# RCM-Comm_v3_E.net
KiCad netlist of a schematic drawn in EAGLE
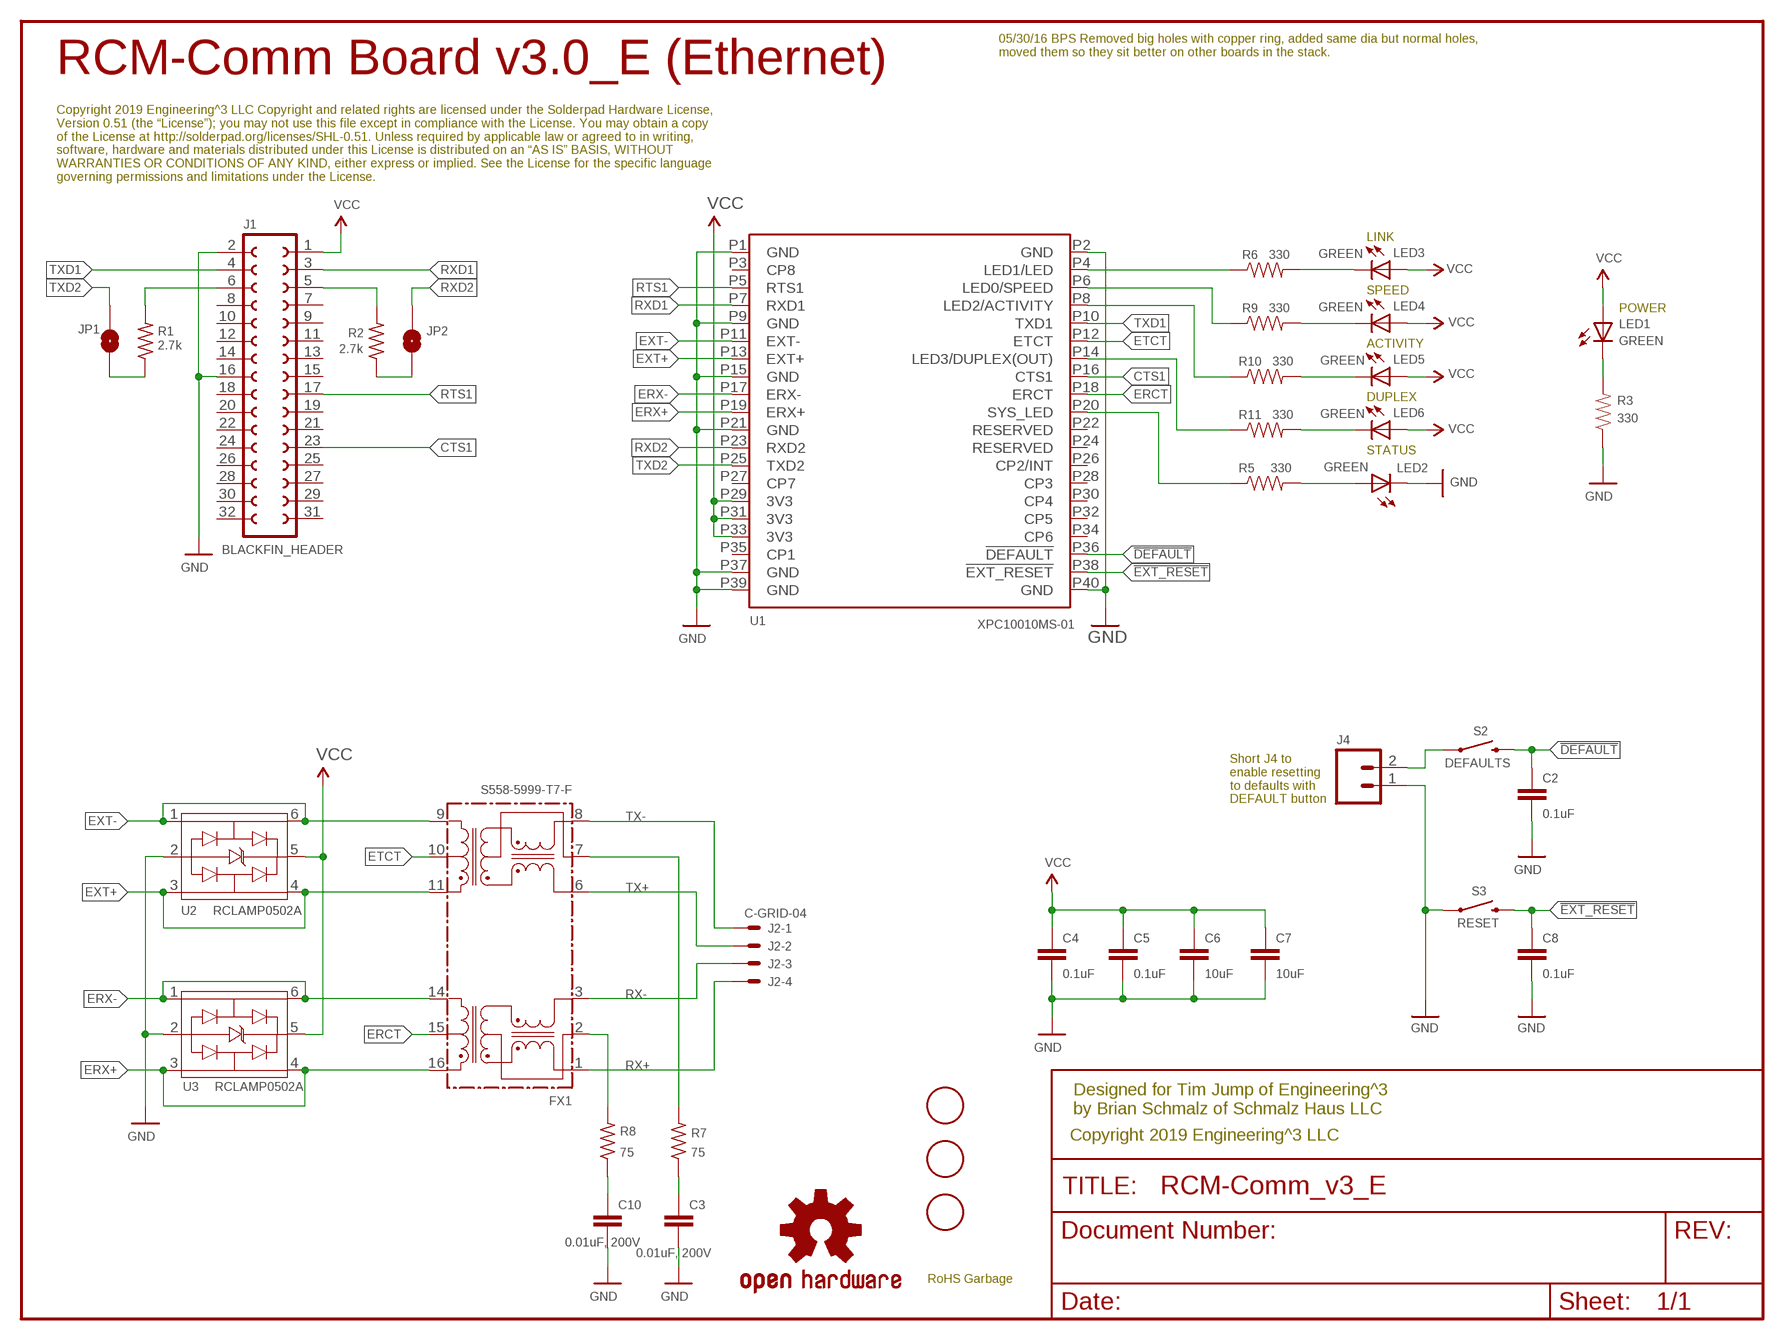
[diagram p0: schematic, sheet 1]

(export (version "E")
  (design (tool "Eeschema 10.0.6"))
  (components
    (comp (ref "C2")
      (value "0.1uF")
      (footprint "eagle-import:0603-CAP")
      (libsource (lib "eagle-import") (part "0.1UF-25V(+80/-20%)(0603)"))
    )
    (comp (ref "C3")
      (value "0.01uF, 200V")
      (footprint "eagle-import:0603-CAP")
      (libsource (lib "eagle-import") (part "CAP0603-CAP"))
    )
    (comp (ref "C4")
      (value "0.1uF")
      (footprint "eagle-import:0603-CAP")
      (libsource (lib "eagle-import") (part "0.1UF-25V(+80/-20%)(0603)"))
    )
    (comp (ref "C5")
      (value "0.1uF")
      (footprint "eagle-import:0603-CAP")
      (libsource (lib "eagle-import") (part "0.1UF-25V(+80/-20%)(0603)"))
    )
    (comp (ref "C6")
      (value "10uF")
      (footprint "eagle-import:0603-CAP")
      (libsource (lib "eagle-import") (part "10UF-6.3V-20%(0603)"))
    )
    (comp (ref "C7")
      (value "10uF")
      (footprint "eagle-import:0603-CAP")
      (libsource (lib "eagle-import") (part "10UF-6.3V-20%(0603)"))
    )
    (comp (ref "C8")
      (value "0.1uF")
      (footprint "eagle-import:0603-CAP")
      (libsource (lib "eagle-import") (part "0.1UF-25V(+80/-20%)(0603)"))
    )
    (comp (ref "C10")
      (value "0.01uF, 200V")
      (footprint "eagle-import:0603-CAP")
      (libsource (lib "eagle-import") (part "CAP0603-CAP"))
    )
    (comp (ref "FID1")
      (value "FIDUCIAL")
      (footprint "eagle-import:FIDUCIAL_1MM")
      (libsource (lib "eagle-import") (part "FIDUCIAL"))
    )
    (comp (ref "FID2")
      (value "FIDUCIAL")
      (footprint "eagle-import:FIDUCIAL_1MM")
      (libsource (lib "eagle-import") (part "FIDUCIAL"))
    )
    (comp (ref "FID3")
      (value "FIDUCIAL")
      (footprint "eagle-import:FIDUCIAL_1MM")
      (libsource (lib "eagle-import") (part "FIDUCIAL"))
    )
    (comp (ref "FX1")
      (value "S558-5999-T7-F")
      (footprint "eagle-import:N5")
      (libsource (lib "eagle-import") (part "TG110-E050N5"))
    )
    (comp (ref "J1")
      (value "BLACKFIN_HEADER")
      (footprint "eagle-import:2X16")
      (libsource (lib "eagle-import") (part "BLACKFIN_HEADER"))
    )
    (comp (ref "J2-")
      (value "C-GRID-04")
      (footprint "eagle-import:70555-04")
      (libsource (lib "eagle-import") (part "C-GRID-04"))
    )
    (comp (ref "J4")
      (value "M02LOCK")
      (footprint "eagle-import:1X02_LOCK")
      (libsource (lib "eagle-import") (part "M02LOCK"))
    )
    (comp (ref "JP1")
      (value "JUMPER-PAD-2-NOROUND")
      (footprint "eagle-import:PAD-JUMPER-2-NO_YES_SILK_ROUND")
      (libsource (lib "eagle-import") (part "JUMPER-PAD-2-NOROUND"))
    )
    (comp (ref "JP2")
      (value "JUMPER-PAD-2-NOROUND")
      (footprint "eagle-import:PAD-JUMPER-2-NO_YES_SILK_ROUND")
      (libsource (lib "eagle-import") (part "JUMPER-PAD-2-NOROUND"))
    )
    (comp (ref "LED1")
      (value "GREEN")
      (footprint "eagle-import:LED-0603")
      (libsource (lib "eagle-import") (part "LED0603"))
    )
    (comp (ref "LED2")
      (value "GREEN")
      (footprint "eagle-import:LED-0603")
      (libsource (lib "eagle-import") (part "LED0603"))
    )
    (comp (ref "LED3")
      (value "GREEN")
      (footprint "eagle-import:LED-0603")
      (libsource (lib "eagle-import") (part "LED0603"))
    )
    (comp (ref "LED4")
      (value "GREEN")
      (footprint "eagle-import:LED-0603")
      (libsource (lib "eagle-import") (part "LED0603"))
    )
    (comp (ref "LED5")
      (value "GREEN")
      (footprint "eagle-import:LED-0603")
      (libsource (lib "eagle-import") (part "LED0603"))
    )
    (comp (ref "LED6")
      (value "GREEN")
      (footprint "eagle-import:LED-0603")
      (libsource (lib "eagle-import") (part "LED0603"))
    )
    (comp (ref "LOGO1")
      (value "OSHW-LOGOM")
      (footprint "eagle-import:OSHW-LOGO-M")
      (libsource (lib "eagle-import") (part "OSHW-LOGOM"))
    )
    (comp (ref "R1")
      (value "2.7k")
      (footprint "eagle-import:R0603")
      (libsource (lib "eagle-import") (part "R-US_R0603"))
    )
    (comp (ref "R2")
      (value "2.7k")
      (footprint "eagle-import:R0603")
      (libsource (lib "eagle-import") (part "R-US_R0603"))
    )
    (comp (ref "R3")
      (value "330")
      (footprint "eagle-import:0603-RES")
      (libsource (lib "eagle-import") (part "RESISTOR0603-RES"))
    )
    (comp (ref "R5")
      (value "330")
      (footprint "eagle-import:0603-RES")
      (libsource (lib "eagle-import") (part "RESISTOR0603-RES"))
    )
    (comp (ref "R6")
      (value "330")
      (footprint "eagle-import:0603-RES")
      (libsource (lib "eagle-import") (part "RESISTOR0603-RES"))
    )
    (comp (ref "R7")
      (value "75")
      (footprint "eagle-import:R0603")
      (libsource (lib "eagle-import") (part "R-US_R0603"))
    )
    (comp (ref "R8")
      (value "75")
      (footprint "eagle-import:R0603")
      (libsource (lib "eagle-import") (part "R-US_R0603"))
    )
    (comp (ref "R9")
      (value "330")
      (footprint "eagle-import:0603-RES")
      (libsource (lib "eagle-import") (part "RESISTOR0603-RES"))
    )
    (comp (ref "R10")
      (value "330")
      (footprint "eagle-import:0603-RES")
      (libsource (lib "eagle-import") (part "RESISTOR0603-RES"))
    )
    (comp (ref "R11")
      (value "330")
      (footprint "eagle-import:0603-RES")
      (libsource (lib "eagle-import") (part "RESISTOR0603-RES"))
    )
    (comp (ref "S2")
      (value "DEFAULTS")
      (footprint "eagle-import:TACTILE-SWITCH-SMD")
      (libsource (lib "eagle-import") (part "SWITCH-MOMENTARY-2SMD"))
    )
    (comp (ref "S3")
      (value "RESET")
      (footprint "eagle-import:TACTILE-SWITCH-SMD")
      (libsource (lib "eagle-import") (part "SWITCH-MOMENTARY-2SMD"))
    )
    (comp (ref "U$3")
      (value "ROHS_GARBAGE")
      (footprint "eagle-import:ROHS_GARBAGE_5MM")
      (libsource (lib "eagle-import") (part "ROHS_GARBAGE"))
    )
    (comp (ref "U1")
      (value "XPC10010MS-01")
      (footprint "eagle-import:LANTRONIX_XPICO")
      (libsource (lib "eagle-import") (part "LANTRONIX_XPICO"))
    )
    (comp (ref "U2")
      (value "RCLAMP0502A")
      (footprint "eagle-import:SC-89")
      (libsource (lib "eagle-import") (part "RCLAMP0502A"))
    )
    (comp (ref "U3")
      (value "RCLAMP0502A")
      (footprint "eagle-import:SC-89")
      (libsource (lib "eagle-import") (part "RCLAMP0502A"))
    )
  )
  (nets
    (net (code "1") (name "/RX+") (class "Default")
      (node (ref "FX1") (pin "1") (pinfunction "1_1") (pintype "passive"))
      (node (ref "J2-") (pin "4") (pinfunction "S_4") (pintype "passive"))
    )
    (net (code "2") (name "/RX-") (class "Default")
      (node (ref "FX1") (pin "3") (pinfunction "3_3") (pintype "passive"))
      (node (ref "J2-") (pin "3") (pinfunction "S_3") (pintype "passive"))
    )
    (net (code "3") (name "/TX+") (class "Default")
      (node (ref "FX1") (pin "6") (pinfunction "6_6") (pintype "passive"))
      (node (ref "J2-") (pin "2") (pinfunction "S_2") (pintype "passive"))
    )
    (net (code "4") (name "/TX-") (class "Default")
      (node (ref "FX1") (pin "8") (pinfunction "8_8") (pintype "passive"))
      (node (ref "J2-") (pin "1") (pinfunction "S_1") (pintype "passive"))
    )
    (net (code "5") (name "/~{DEFAULT}") (class "Default")
      (node (ref "C2") (pin "1") (pinfunction "1_1") (pintype "passive"))
      (node (ref "S2") (pin "3") (pinfunction "2_3") (pintype "passive"))
      (node (ref "U1") (pin "P36") (pinfunction "~{DEFAULT}_P36") (pintype "bidirectional"))
    )
    (net (code "6") (name "/~{EXT_RESET}") (class "Default")
      (node (ref "C8") (pin "1") (pinfunction "1_1") (pintype "passive"))
      (node (ref "S3") (pin "3") (pinfunction "2_3") (pintype "passive"))
      (node (ref "U1") (pin "P38") (pinfunction "~{EXT_RESET}_P38") (pintype "bidirectional"))
    )
    (net (code "7") (name "CTS1") (class "Default")
      (node (ref "J1") (pin "23") (pinfunction "GP6_23") (pintype "passive"))
      (node (ref "U1") (pin "P16") (pinfunction "CTS1_P16") (pintype "bidirectional"))
    )
    (net (code "8") (name "ERCT") (class "Default")
      (node (ref "FX1") (pin "15") (pinfunction "15_15") (pintype "passive"))
      (node (ref "U1") (pin "P18") (pinfunction "ERCT_P18") (pintype "bidirectional"))
    )
    (net (code "9") (name "ERX+") (class "Default")
      (node (ref "FX1") (pin "16") (pinfunction "16_16") (pintype "passive"))
      (node (ref "U1") (pin "P19") (pinfunction "ERX+_P19") (pintype "bidirectional"))
      (node (ref "U3") (pin "3") (pinfunction "P$3_3") (pintype "bidirectional"))
      (node (ref "U3") (pin "4") (pinfunction "P$4_4") (pintype "bidirectional"))
    )
    (net (code "10") (name "ERX-") (class "Default")
      (node (ref "FX1") (pin "14") (pinfunction "14_14") (pintype "passive"))
      (node (ref "U1") (pin "P17") (pinfunction "ERX-_P17") (pintype "bidirectional"))
      (node (ref "U3") (pin "1") (pinfunction "P$1_1") (pintype "bidirectional"))
      (node (ref "U3") (pin "6") (pinfunction "P$6_6") (pintype "bidirectional"))
    )
    (net (code "11") (name "ETCT") (class "Default")
      (node (ref "FX1") (pin "10") (pinfunction "10_10") (pintype "passive"))
      (node (ref "U1") (pin "P12") (pinfunction "ETCT_P12") (pintype "bidirectional"))
    )
    (net (code "12") (name "EXT+") (class "Default")
      (node (ref "FX1") (pin "11") (pinfunction "11_11") (pintype "passive"))
      (node (ref "U1") (pin "P13") (pinfunction "EXT+_P13") (pintype "bidirectional"))
      (node (ref "U2") (pin "3") (pinfunction "P$3_3") (pintype "bidirectional"))
      (node (ref "U2") (pin "4") (pinfunction "P$4_4") (pintype "bidirectional"))
    )
    (net (code "13") (name "EXT-") (class "Default")
      (node (ref "FX1") (pin "9") (pinfunction "9_9") (pintype "passive"))
      (node (ref "U1") (pin "P11") (pinfunction "EXT-_P11") (pintype "bidirectional"))
      (node (ref "U2") (pin "1") (pinfunction "P$1_1") (pintype "bidirectional"))
      (node (ref "U2") (pin "6") (pinfunction "P$6_6") (pintype "bidirectional"))
    )
    (net (code "14") (name "GND") (class "Default")
      (node (ref "C10") (pin "2") (pinfunction "2_2") (pintype "passive"))
      (node (ref "C2") (pin "2") (pinfunction "2_2") (pintype "passive"))
      (node (ref "C3") (pin "2") (pinfunction "2_2") (pintype "passive"))
      (node (ref "C4") (pin "2") (pinfunction "2_2") (pintype "passive"))
      (node (ref "C5") (pin "2") (pinfunction "2_2") (pintype "passive"))
      (node (ref "C6") (pin "2") (pinfunction "2_2") (pintype "passive"))
      (node (ref "C7") (pin "2") (pinfunction "2_2") (pintype "passive"))
      (node (ref "C8") (pin "2") (pinfunction "2_2") (pintype "passive"))
      (node (ref "J1") (pin "16") (pinfunction "GND16_16") (pintype "passive"))
      (node (ref "J1") (pin "2") (pinfunction "GND_2") (pintype "passive"))
      (node (ref "J4") (pin "1") (pinfunction "1_1") (pintype "passive"))
      (node (ref "LED2") (pin "C") (pinfunction "C_C") (pintype "passive"))
      (node (ref "R3") (pin "1") (pinfunction "1_1") (pintype "passive"))
      (node (ref "S3") (pin "1") (pinfunction "1_1") (pintype "passive"))
      (node (ref "U1") (pin "P1") (pinfunction "GND_P1") (pintype "bidirectional"))
      (node (ref "U1") (pin "P15") (pinfunction "GND_P15") (pintype "bidirectional"))
      (node (ref "U1") (pin "P2") (pinfunction "GND_P2") (pintype "bidirectional"))
      (node (ref "U1") (pin "P21") (pinfunction "GND_P21") (pintype "bidirectional"))
      (node (ref "U1") (pin "P37") (pinfunction "GND_P37") (pintype "bidirectional"))
      (node (ref "U1") (pin "P39") (pinfunction "GND_P39") (pintype "bidirectional"))
      (node (ref "U1") (pin "P40") (pinfunction "GND_P40") (pintype "bidirectional"))
      (node (ref "U1") (pin "P9") (pinfunction "GND_P9") (pintype "bidirectional"))
      (node (ref "U2") (pin "2") (pinfunction "P$2_2") (pintype "bidirectional"))
      (node (ref "U3") (pin "2") (pinfunction "P$2_2") (pintype "bidirectional"))
    )
    (net (code "15") (name "Net-(C3-Pad1)") (class "Default")
      (node (ref "C3") (pin "1") (pinfunction "1_1") (pintype "passive"))
      (node (ref "R7") (pin "1") (pinfunction "1_1") (pintype "passive"))
    )
    (net (code "16") (name "Net-(C10-Pad1)") (class "Default")
      (node (ref "C10") (pin "1") (pinfunction "1_1") (pintype "passive"))
      (node (ref "R8") (pin "1") (pinfunction "1_1") (pintype "passive"))
    )
    (net (code "17") (name "Net-(FX1-Pad2)") (class "Default")
      (node (ref "FX1") (pin "2") (pinfunction "2_2") (pintype "passive"))
      (node (ref "R8") (pin "2") (pinfunction "2_2") (pintype "passive"))
    )
    (net (code "18") (name "Net-(FX1-Pad7)") (class "Default")
      (node (ref "FX1") (pin "7") (pinfunction "7_7") (pintype "passive"))
      (node (ref "R7") (pin "2") (pinfunction "2_2") (pintype "passive"))
    )
    (net (code "19") (name "Net-(J1-RX1)") (class "Default")
      (node (ref "J1") (pin "6") (pinfunction "RX1_6") (pintype "passive"))
      (node (ref "R1") (pin "2") (pinfunction "2_2") (pintype "passive"))
    )
    (net (code "20") (name "Net-(J1-TX1)") (class "Default")
      (node (ref "J1") (pin "5") (pinfunction "TX1_5") (pintype "passive"))
      (node (ref "R2") (pin "2") (pinfunction "2_2") (pintype "passive"))
    )
    (net (code "21") (name "Net-(J4-Pad2)") (class "Default")
      (node (ref "J4") (pin "2") (pinfunction "2_2") (pintype "passive"))
      (node (ref "S2") (pin "1") (pinfunction "1_1") (pintype "passive"))
    )
    (net (code "22") (name "Net-(JP1-Pad2)") (class "Default")
      (node (ref "JP1") (pin "2") (pinfunction "2_2") (pintype "passive"))
      (node (ref "R1") (pin "1") (pinfunction "1_1") (pintype "passive"))
    )
    (net (code "23") (name "Net-(JP2-Pad1)") (class "Default")
      (node (ref "JP2") (pin "1") (pinfunction "1_1") (pintype "passive"))
      (node (ref "R2") (pin "1") (pinfunction "1_1") (pintype "passive"))
    )
    (net (code "24") (name "Net-(LED1-PadC)") (class "Default")
      (node (ref "LED1") (pin "C") (pinfunction "C_C") (pintype "passive"))
      (node (ref "R3") (pin "2") (pinfunction "2_2") (pintype "passive"))
    )
    (net (code "25") (name "Net-(LED2-PadA)") (class "Default")
      (node (ref "LED2") (pin "A") (pinfunction "A_A") (pintype "passive"))
      (node (ref "R5") (pin "2") (pinfunction "2_2") (pintype "passive"))
    )
    (net (code "26") (name "Net-(LED3-PadC)") (class "Default")
      (node (ref "LED3") (pin "C") (pinfunction "C_C") (pintype "passive"))
      (node (ref "R6") (pin "2") (pinfunction "2_2") (pintype "passive"))
    )
    (net (code "27") (name "Net-(LED4-PadC)") (class "Default")
      (node (ref "LED4") (pin "C") (pinfunction "C_C") (pintype "passive"))
      (node (ref "R9") (pin "2") (pinfunction "2_2") (pintype "passive"))
    )
    (net (code "28") (name "Net-(LED5-PadC)") (class "Default")
      (node (ref "LED5") (pin "C") (pinfunction "C_C") (pintype "passive"))
      (node (ref "R10") (pin "2") (pinfunction "2_2") (pintype "passive"))
    )
    (net (code "29") (name "Net-(LED6-PadC)") (class "Default")
      (node (ref "LED6") (pin "C") (pinfunction "C_C") (pintype "passive"))
      (node (ref "R11") (pin "2") (pinfunction "2_2") (pintype "passive"))
    )
    (net (code "30") (name "Net-(U1-LED0{slash}SPEED)") (class "Default")
      (node (ref "R9") (pin "1") (pinfunction "1_1") (pintype "passive"))
      (node (ref "U1") (pin "P6") (pinfunction "LED0/SPEED_P6") (pintype "bidirectional"))
    )
    (net (code "31") (name "Net-(U1-LED1{slash}LED)") (class "Default")
      (node (ref "R6") (pin "1") (pinfunction "1_1") (pintype "passive"))
      (node (ref "U1") (pin "P4") (pinfunction "LED1/LED_P4") (pintype "bidirectional"))
    )
    (net (code "32") (name "Net-(U1-LED2{slash}ACTIVITY)") (class "Default")
      (node (ref "R10") (pin "1") (pinfunction "1_1") (pintype "passive"))
      (node (ref "U1") (pin "P8") (pinfunction "LED2/ACTIVITY_P8") (pintype "bidirectional"))
    )
    (net (code "33") (name "Net-(U1-LED3{slash}DUPLEX(OUT))") (class "Default")
      (node (ref "R11") (pin "1") (pinfunction "1_1") (pintype "passive"))
      (node (ref "U1") (pin "P14") (pinfunction "LED3/DUPLEX(OUT)_P14") (pintype "bidirectional"))
    )
    (net (code "34") (name "Net-(U1-SYS_LED)") (class "Default")
      (node (ref "R5") (pin "1") (pinfunction "1_1") (pintype "passive"))
      (node (ref "U1") (pin "P20") (pinfunction "SYS_LED_P20") (pintype "bidirectional"))
    )
    (net (code "35") (name "RTS1") (class "Default")
      (node (ref "J1") (pin "17") (pinfunction "GP0_17") (pintype "passive"))
      (node (ref "U1") (pin "P5") (pinfunction "RTS1_P5") (pintype "bidirectional"))
    )
    (net (code "36") (name "RXD1") (class "Default")
      (node (ref "J1") (pin "3") (pinfunction "TX0_3") (pintype "passive"))
      (node (ref "U1") (pin "P7") (pinfunction "RXD1_P7") (pintype "bidirectional"))
    )
    (net (code "37") (name "RXD2") (class "Default")
      (node (ref "JP2") (pin "2") (pinfunction "2_2") (pintype "passive"))
      (node (ref "U1") (pin "P23") (pinfunction "RXD2_P23") (pintype "bidirectional"))
    )
    (net (code "38") (name "TXD1") (class "Default")
      (node (ref "J1") (pin "4") (pinfunction "RX0_4") (pintype "passive"))
      (node (ref "U1") (pin "P10") (pinfunction "TXD1_P10") (pintype "bidirectional"))
    )
    (net (code "39") (name "TXD2") (class "Default")
      (node (ref "JP1") (pin "1") (pinfunction "1_1") (pintype "passive"))
      (node (ref "U1") (pin "P25") (pinfunction "TXD2_P25") (pintype "bidirectional"))
    )
    (net (code "40") (name "VCC") (class "Default")
      (node (ref "C4") (pin "1") (pinfunction "1_1") (pintype "passive"))
      (node (ref "C5") (pin "1") (pinfunction "1_1") (pintype "passive"))
      (node (ref "C6") (pin "1") (pinfunction "1_1") (pintype "passive"))
      (node (ref "C7") (pin "1") (pinfunction "1_1") (pintype "passive"))
      (node (ref "J1") (pin "1") (pinfunction "3.3V_1") (pintype "passive"))
      (node (ref "LED1") (pin "A") (pinfunction "A_A") (pintype "passive"))
      (node (ref "LED3") (pin "A") (pinfunction "A_A") (pintype "passive"))
      (node (ref "LED4") (pin "A") (pinfunction "A_A") (pintype "passive"))
      (node (ref "LED5") (pin "A") (pinfunction "A_A") (pintype "passive"))
      (node (ref "LED6") (pin "A") (pinfunction "A_A") (pintype "passive"))
      (node (ref "U1") (pin "P29") (pinfunction "3V3_P29") (pintype "bidirectional"))
      (node (ref "U1") (pin "P31") (pinfunction "3V3_P31") (pintype "bidirectional"))
      (node (ref "U1") (pin "P33") (pinfunction "3V3_P33") (pintype "bidirectional"))
      (node (ref "U2") (pin "5") (pinfunction "P$5_5") (pintype "bidirectional"))
      (node (ref "U3") (pin "5") (pinfunction "P$5_5") (pintype "bidirectional"))
    )
    (net (code "41") (name "unconnected-(J1-GP1-Pad18)") (class "Default")
      (node (ref "J1") (pin "18") (pinfunction "GP1_18") (pintype "passive"))
    )
    (net (code "42") (name "unconnected-(J1-GP2-Pad19)") (class "Default")
      (node (ref "J1") (pin "19") (pinfunction "GP2_19") (pintype "passive"))
    )
    (net (code "43") (name "unconnected-(J1-GP3-Pad20)") (class "Default")
      (node (ref "J1") (pin "20") (pinfunction "GP3_20") (pintype "passive"))
    )
    (net (code "44") (name "unconnected-(J1-GP4-Pad21)") (class "Default")
      (node (ref "J1") (pin "21") (pinfunction "GP4_21") (pintype "passive"))
    )
    (net (code "45") (name "unconnected-(J1-GP5-Pad22)") (class "Default")
      (node (ref "J1") (pin "22") (pinfunction "GP5_22") (pintype "passive"))
    )
    (net (code "46") (name "unconnected-(J1-GP7-Pad24)") (class "Default")
      (node (ref "J1") (pin "24") (pinfunction "GP7_24") (pintype "passive"))
    )
    (net (code "47") (name "unconnected-(J1-GP8-Pad25)") (class "Default")
      (node (ref "J1") (pin "25") (pinfunction "GP8_25") (pintype "passive"))
    )
    (net (code "48") (name "unconnected-(J1-GP9-Pad26)") (class "Default")
      (node (ref "J1") (pin "26") (pinfunction "GP9_26") (pintype "passive"))
    )
    (net (code "49") (name "unconnected-(J1-GPA-Pad27)") (class "Default")
      (node (ref "J1") (pin "27") (pinfunction "GPA_27") (pintype "passive"))
    )
    (net (code "50") (name "unconnected-(J1-GPB-Pad28)") (class "Default")
      (node (ref "J1") (pin "28") (pinfunction "GPB_28") (pintype "passive"))
    )
    (net (code "51") (name "unconnected-(J1-GPC-Pad29)") (class "Default")
      (node (ref "J1") (pin "29") (pinfunction "GPC_29") (pintype "passive"))
    )
    (net (code "52") (name "unconnected-(J1-GPD-Pad30)") (class "Default")
      (node (ref "J1") (pin "30") (pinfunction "GPD_30") (pintype "passive"))
    )
    (net (code "53") (name "unconnected-(J1-GPE-Pad31)") (class "Default")
      (node (ref "J1") (pin "31") (pinfunction "GPE_31") (pintype "passive"))
    )
    (net (code "54") (name "unconnected-(J1-GPF-Pad32)") (class "Default")
      (node (ref "J1") (pin "32") (pinfunction "GPF_32") (pintype "passive"))
    )
    (net (code "55") (name "unconnected-(J1-I2C_SDA-Pad15)") (class "Default")
      (node (ref "J1") (pin "15") (pinfunction "I2C_SDA_15") (pintype "passive"))
    )
    (net (code "56") (name "unconnected-(J1-SPI_MISO-Pad10)") (class "Default")
      (node (ref "J1") (pin "10") (pinfunction "SPI_MISO_10") (pintype "passive"))
    )
    (net (code "57") (name "unconnected-(J1-SPI_MOSI-Pad9)") (class "Default")
      (node (ref "J1") (pin "9") (pinfunction "SPI_MOSI_9") (pintype "passive"))
    )
    (net (code "58") (name "unconnected-(J1-SPI_SCK-Pad11)") (class "Default")
      (node (ref "J1") (pin "11") (pinfunction "SPI_SCK_11") (pintype "passive"))
    )
    (net (code "59") (name "unconnected-(J1-SPI_SCL-Pad14)") (class "Default")
      (node (ref "J1") (pin "14") (pinfunction "SPI_SCL_14") (pintype "passive"))
    )
    (net (code "60") (name "unconnected-(J1-SPI_SEL-Pad12)") (class "Default")
      (node (ref "J1") (pin "12") (pinfunction "SPI_SEL_12") (pintype "passive"))
    )
    (net (code "61") (name "unconnected-(J1-SPI_SEL2-Pad13)") (class "Default")
      (node (ref "J1") (pin "13") (pinfunction "SPI_SEL2_13") (pintype "passive"))
    )
    (net (code "62") (name "unconnected-(J1-TMR2-Pad7)") (class "Default")
      (node (ref "J1") (pin "7") (pinfunction "TMR2_7") (pintype "passive"))
    )
    (net (code "63") (name "unconnected-(J1-TMR3-Pad8)") (class "Default")
      (node (ref "J1") (pin "8") (pinfunction "TMR3_8") (pintype "passive"))
    )
    (net (code "64") (name "unconnected-(U1-CP1-PadP35)") (class "Default")
      (node (ref "U1") (pin "P35") (pinfunction "CP1_P35") (pintype "bidirectional"))
    )
    (net (code "65") (name "unconnected-(U1-CP2{slash}INT-PadP26)") (class "Default")
      (node (ref "U1") (pin "P26") (pinfunction "CP2/INT_P26") (pintype "bidirectional"))
    )
    (net (code "66") (name "unconnected-(U1-CP3-PadP28)") (class "Default")
      (node (ref "U1") (pin "P28") (pinfunction "CP3_P28") (pintype "bidirectional"))
    )
    (net (code "67") (name "unconnected-(U1-CP4-PadP30)") (class "Default")
      (node (ref "U1") (pin "P30") (pinfunction "CP4_P30") (pintype "bidirectional"))
    )
    (net (code "68") (name "unconnected-(U1-CP5-PadP32)") (class "Default")
      (node (ref "U1") (pin "P32") (pinfunction "CP5_P32") (pintype "bidirectional"))
    )
    (net (code "69") (name "unconnected-(U1-CP6-PadP34)") (class "Default")
      (node (ref "U1") (pin "P34") (pinfunction "CP6_P34") (pintype "bidirectional"))
    )
    (net (code "70") (name "unconnected-(U1-CP7-PadP27)") (class "Default")
      (node (ref "U1") (pin "P27") (pinfunction "CP7_P27") (pintype "bidirectional"))
    )
    (net (code "71") (name "unconnected-(U1-CP8-PadP3)") (class "Default")
      (node (ref "U1") (pin "P3") (pinfunction "CP8_P3") (pintype "bidirectional"))
    )
    (net (code "72") (name "unconnected-(U1-RESERVED-PadP22)") (class "Default")
      (node (ref "U1") (pin "P22") (pinfunction "RESERVED_P22") (pintype "bidirectional"))
    )
    (net (code "73") (name "unconnected-(U1-RESERVED-PadP24)") (class "Default")
      (node (ref "U1") (pin "P24") (pinfunction "RESERVED_P24") (pintype "bidirectional"))
    )
  )
)
